# SIDEPANELV5_old.net
KiCad netlist of a schematic drawn in EAGLE
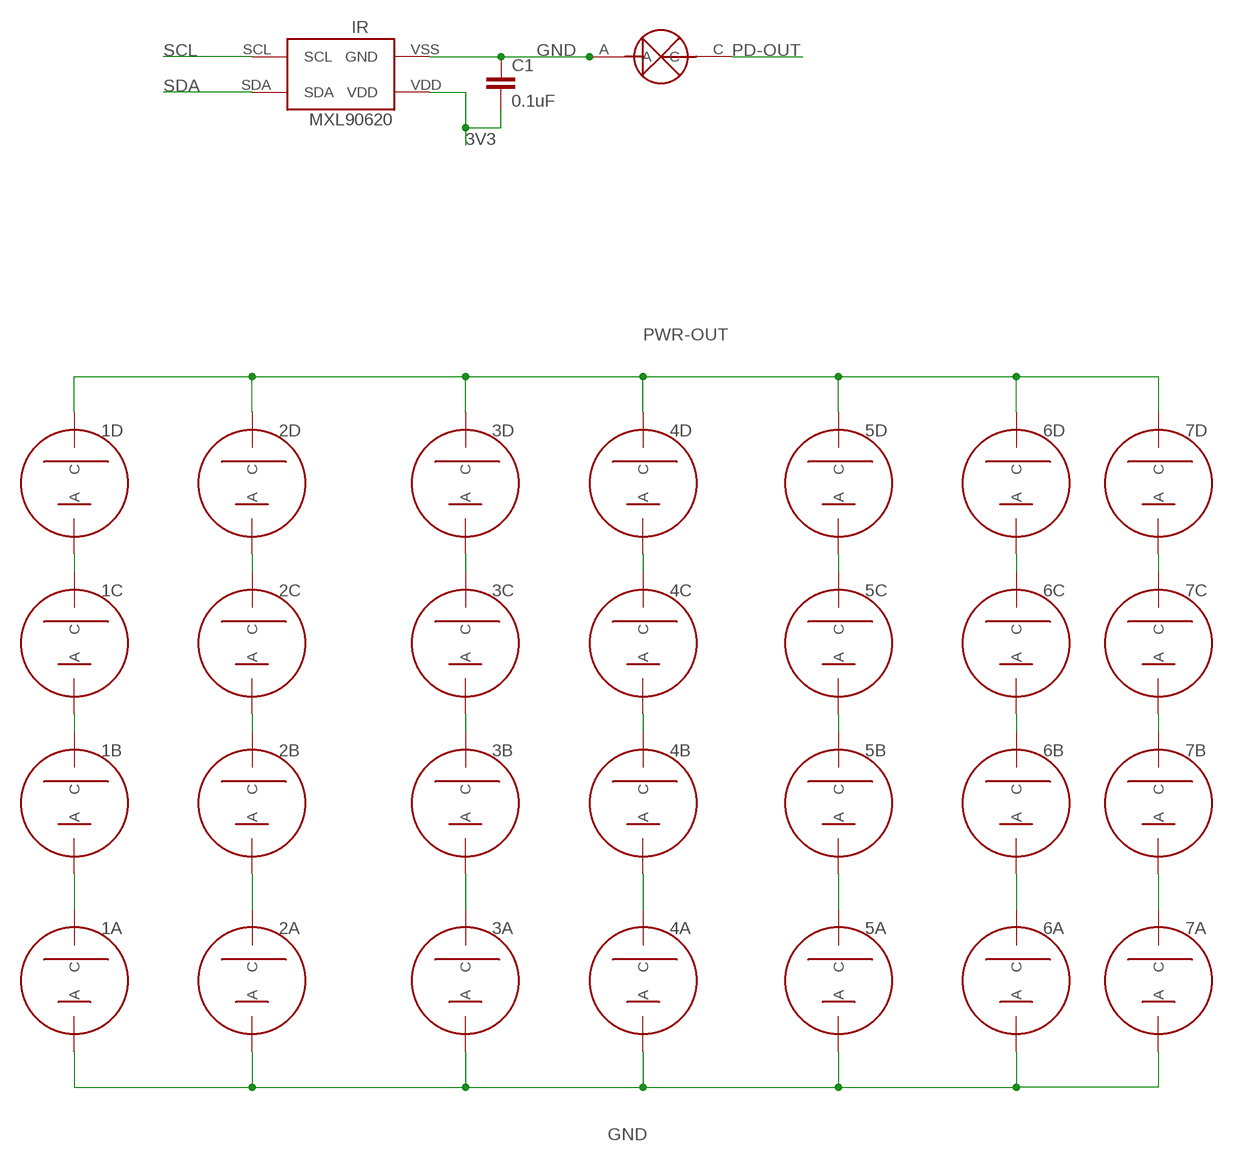
[diagram p0: schematic, sheet 1]

(export (version "E")
  (design (tool "Eeschema 10.0.6"))
  (components
    (comp (ref "1A")
      (value "SOLARCELLV3")
      (footprint "eagle-import:TRISOLX-V3")
      (libsource (lib "eagle-import") (part "SOLARCELLV3"))
    )
    (comp (ref "1B")
      (value "SOLARCELLV3")
      (footprint "eagle-import:TRISOLX-V3")
      (libsource (lib "eagle-import") (part "SOLARCELLV3"))
    )
    (comp (ref "1C")
      (value "SOLARCELLV3")
      (footprint "eagle-import:TRISOLX-V3")
      (libsource (lib "eagle-import") (part "SOLARCELLV3"))
    )
    (comp (ref "1D")
      (value "SOLARCELLV3")
      (footprint "eagle-import:TRISOLX-V3")
      (libsource (lib "eagle-import") (part "SOLARCELLV3"))
    )
    (comp (ref "2A")
      (value "SOLARCELLV3")
      (footprint "eagle-import:TRISOLX-V3")
      (libsource (lib "eagle-import") (part "SOLARCELLV3"))
    )
    (comp (ref "2B")
      (value "SOLARCELLV3")
      (footprint "eagle-import:TRISOLX-V3")
      (libsource (lib "eagle-import") (part "SOLARCELLV3"))
    )
    (comp (ref "2C")
      (value "SOLARCELLV3")
      (footprint "eagle-import:TRISOLX-V3")
      (libsource (lib "eagle-import") (part "SOLARCELLV3"))
    )
    (comp (ref "2D")
      (value "SOLARCELLV3")
      (footprint "eagle-import:TRISOLX-V3")
      (libsource (lib "eagle-import") (part "SOLARCELLV3"))
    )
    (comp (ref "3A")
      (value "SOLARCELLV3")
      (footprint "eagle-import:TRISOLX-V3")
      (libsource (lib "eagle-import") (part "SOLARCELLV3"))
    )
    (comp (ref "3B")
      (value "SOLARCELLV3")
      (footprint "eagle-import:TRISOLX-V3")
      (libsource (lib "eagle-import") (part "SOLARCELLV3"))
    )
    (comp (ref "3C")
      (value "SOLARCELLV3")
      (footprint "eagle-import:TRISOLX-V3")
      (libsource (lib "eagle-import") (part "SOLARCELLV3"))
    )
    (comp (ref "3D")
      (value "SOLARCELLV3")
      (footprint "eagle-import:TRISOLX-V3")
      (libsource (lib "eagle-import") (part "SOLARCELLV3"))
    )
    (comp (ref "4A")
      (value "SOLARCELLV3")
      (footprint "eagle-import:TRISOLX-V3")
      (libsource (lib "eagle-import") (part "SOLARCELLV3"))
    )
    (comp (ref "4B")
      (value "SOLARCELLV3")
      (footprint "eagle-import:TRISOLX-V3")
      (libsource (lib "eagle-import") (part "SOLARCELLV3"))
    )
    (comp (ref "4C")
      (value "SOLARCELLV3")
      (footprint "eagle-import:TRISOLX-V3")
      (libsource (lib "eagle-import") (part "SOLARCELLV3"))
    )
    (comp (ref "4D")
      (value "SOLARCELLV3")
      (footprint "eagle-import:TRISOLX-V3")
      (libsource (lib "eagle-import") (part "SOLARCELLV3"))
    )
    (comp (ref "5A")
      (value "SOLARCELLV3")
      (footprint "eagle-import:TRISOLX-V3")
      (libsource (lib "eagle-import") (part "SOLARCELLV3"))
    )
    (comp (ref "5B")
      (value "SOLARCELLV3")
      (footprint "eagle-import:TRISOLX-V3")
      (libsource (lib "eagle-import") (part "SOLARCELLV3"))
    )
    (comp (ref "5C")
      (value "SOLARCELLV3")
      (footprint "eagle-import:TRISOLX-V3")
      (libsource (lib "eagle-import") (part "SOLARCELLV3"))
    )
    (comp (ref "5D")
      (value "SOLARCELLV3")
      (footprint "eagle-import:TRISOLX-V3")
      (libsource (lib "eagle-import") (part "SOLARCELLV3"))
    )
    (comp (ref "6A")
      (value "SOLARCELLV3")
      (footprint "eagle-import:TRISOLX-V3")
      (libsource (lib "eagle-import") (part "SOLARCELLV3"))
    )
    (comp (ref "6B")
      (value "SOLARCELLV3")
      (footprint "eagle-import:TRISOLX-V3")
      (libsource (lib "eagle-import") (part "SOLARCELLV3"))
    )
    (comp (ref "6C")
      (value "SOLARCELLV3")
      (footprint "eagle-import:TRISOLX-V3")
      (libsource (lib "eagle-import") (part "SOLARCELLV3"))
    )
    (comp (ref "6D")
      (value "SOLARCELLV3")
      (footprint "eagle-import:TRISOLX-V3")
      (libsource (lib "eagle-import") (part "SOLARCELLV3"))
    )
    (comp (ref "7A")
      (value "SOLARCELLV3")
      (footprint "eagle-import:TRISOLX-V3")
      (libsource (lib "eagle-import") (part "SOLARCELLV3"))
    )
    (comp (ref "7B")
      (value "SOLARCELLV3")
      (footprint "eagle-import:TRISOLX-V3")
      (libsource (lib "eagle-import") (part "SOLARCELLV3"))
    )
    (comp (ref "7C")
      (value "SOLARCELLV3")
      (footprint "eagle-import:TRISOLX-V3")
      (libsource (lib "eagle-import") (part "SOLARCELLV3"))
    )
    (comp (ref "7D")
      (value "SOLARCELLV3")
      (footprint "eagle-import:TRISOLX-V3")
      (libsource (lib "eagle-import") (part "SOLARCELLV3"))
    )
    (comp (ref "C1")
      (value "0.1uF")
      (footprint "eagle-import:0805")
      (libsource (lib "eagle-import") (part "CAP0805"))
    )
    (comp (ref "IR")
      (value "MXL90620")
      (footprint "eagle-import:MXL90620")
      (libsource (lib "eagle-import") (part "MXL90620"))
    )
    (comp (ref "PD")
      (value "PHOTODETECTOR")
      (footprint "eagle-import:PHOTODECTORDEVICE2")
      (libsource (lib "eagle-import") (part "PHOTODETECTOR"))
    )
  )
  (nets
    (net (code "1") (name "/3V3") (class "Default")
      (node (ref "C1") (pin "2") (pinfunction "2_2") (pintype "passive"))
      (node (ref "IR") (pin "VDD") (pinfunction "VDD_VDD") (pintype "bidirectional"))
    )
    (net (code "2") (name "/GND") (class "Default")
      (node (ref "1A") (pin "ANODE") (pinfunction "A_ANODE") (pintype "bidirectional"))
      (node (ref "2A") (pin "ANODE") (pinfunction "A_ANODE") (pintype "bidirectional"))
      (node (ref "3A") (pin "ANODE") (pinfunction "A_ANODE") (pintype "bidirectional"))
      (node (ref "4A") (pin "ANODE") (pinfunction "A_ANODE") (pintype "bidirectional"))
      (node (ref "5A") (pin "ANODE") (pinfunction "A_ANODE") (pintype "bidirectional"))
      (node (ref "6A") (pin "ANODE") (pinfunction "A_ANODE") (pintype "bidirectional"))
      (node (ref "7A") (pin "ANODE") (pinfunction "A_ANODE") (pintype "bidirectional"))
      (node (ref "C1") (pin "1") (pinfunction "1_1") (pintype "passive"))
      (node (ref "IR") (pin "VSS") (pinfunction "GND_VSS") (pintype "bidirectional"))
      (node (ref "PD") (pin "A") (pinfunction "A_A") (pintype "bidirectional"))
    )
    (net (code "3") (name "/PD-OUT") (class "Default")
      (node (ref "PD") (pin "C") (pinfunction "C_C") (pintype "bidirectional"))
    )
    (net (code "4") (name "/PWR-OUT") (class "Default")
      (node (ref "1D") (pin "CATHODE") (pinfunction "C_CATHODE") (pintype "bidirectional"))
      (node (ref "2D") (pin "CATHODE") (pinfunction "C_CATHODE") (pintype "bidirectional"))
      (node (ref "3D") (pin "CATHODE") (pinfunction "C_CATHODE") (pintype "bidirectional"))
      (node (ref "4D") (pin "CATHODE") (pinfunction "C_CATHODE") (pintype "bidirectional"))
      (node (ref "5D") (pin "CATHODE") (pinfunction "C_CATHODE") (pintype "bidirectional"))
      (node (ref "6D") (pin "CATHODE") (pinfunction "C_CATHODE") (pintype "bidirectional"))
      (node (ref "7D") (pin "CATHODE") (pinfunction "C_CATHODE") (pintype "bidirectional"))
    )
    (net (code "5") (name "/SCL") (class "Default")
      (node (ref "IR") (pin "SCL") (pinfunction "SCL_SCL") (pintype "bidirectional"))
    )
    (net (code "6") (name "/SDA") (class "Default")
      (node (ref "IR") (pin "SDA") (pinfunction "SDA_SDA") (pintype "bidirectional"))
    )
    (net (code "7") (name "Net-(1A-C)") (class "Default")
      (node (ref "1A") (pin "CATHODE") (pinfunction "C_CATHODE") (pintype "bidirectional"))
      (node (ref "1B") (pin "ANODE") (pinfunction "A_ANODE") (pintype "bidirectional"))
    )
    (net (code "8") (name "Net-(1B-C)") (class "Default")
      (node (ref "1B") (pin "CATHODE") (pinfunction "C_CATHODE") (pintype "bidirectional"))
      (node (ref "1C") (pin "ANODE") (pinfunction "A_ANODE") (pintype "bidirectional"))
    )
    (net (code "9") (name "Net-(1C-C)") (class "Default")
      (node (ref "1C") (pin "CATHODE") (pinfunction "C_CATHODE") (pintype "bidirectional"))
      (node (ref "1D") (pin "ANODE") (pinfunction "A_ANODE") (pintype "bidirectional"))
    )
    (net (code "10") (name "Net-(2A-C)") (class "Default")
      (node (ref "2A") (pin "CATHODE") (pinfunction "C_CATHODE") (pintype "bidirectional"))
      (node (ref "2B") (pin "ANODE") (pinfunction "A_ANODE") (pintype "bidirectional"))
    )
    (net (code "11") (name "Net-(2B-C)") (class "Default")
      (node (ref "2B") (pin "CATHODE") (pinfunction "C_CATHODE") (pintype "bidirectional"))
      (node (ref "2C") (pin "ANODE") (pinfunction "A_ANODE") (pintype "bidirectional"))
    )
    (net (code "12") (name "Net-(2C-C)") (class "Default")
      (node (ref "2C") (pin "CATHODE") (pinfunction "C_CATHODE") (pintype "bidirectional"))
      (node (ref "2D") (pin "ANODE") (pinfunction "A_ANODE") (pintype "bidirectional"))
    )
    (net (code "13") (name "Net-(3A-C)") (class "Default")
      (node (ref "3A") (pin "CATHODE") (pinfunction "C_CATHODE") (pintype "bidirectional"))
      (node (ref "3B") (pin "ANODE") (pinfunction "A_ANODE") (pintype "bidirectional"))
    )
    (net (code "14") (name "Net-(3B-C)") (class "Default")
      (node (ref "3B") (pin "CATHODE") (pinfunction "C_CATHODE") (pintype "bidirectional"))
      (node (ref "3C") (pin "ANODE") (pinfunction "A_ANODE") (pintype "bidirectional"))
    )
    (net (code "15") (name "Net-(3C-C)") (class "Default")
      (node (ref "3C") (pin "CATHODE") (pinfunction "C_CATHODE") (pintype "bidirectional"))
      (node (ref "3D") (pin "ANODE") (pinfunction "A_ANODE") (pintype "bidirectional"))
    )
    (net (code "16") (name "Net-(4A-C)") (class "Default")
      (node (ref "4A") (pin "CATHODE") (pinfunction "C_CATHODE") (pintype "bidirectional"))
      (node (ref "4B") (pin "ANODE") (pinfunction "A_ANODE") (pintype "bidirectional"))
    )
    (net (code "17") (name "Net-(4B-C)") (class "Default")
      (node (ref "4B") (pin "CATHODE") (pinfunction "C_CATHODE") (pintype "bidirectional"))
      (node (ref "4C") (pin "ANODE") (pinfunction "A_ANODE") (pintype "bidirectional"))
    )
    (net (code "18") (name "Net-(4C-C)") (class "Default")
      (node (ref "4C") (pin "CATHODE") (pinfunction "C_CATHODE") (pintype "bidirectional"))
      (node (ref "4D") (pin "ANODE") (pinfunction "A_ANODE") (pintype "bidirectional"))
    )
    (net (code "19") (name "Net-(5A-C)") (class "Default")
      (node (ref "5A") (pin "CATHODE") (pinfunction "C_CATHODE") (pintype "bidirectional"))
      (node (ref "5B") (pin "ANODE") (pinfunction "A_ANODE") (pintype "bidirectional"))
    )
    (net (code "20") (name "Net-(5B-C)") (class "Default")
      (node (ref "5B") (pin "CATHODE") (pinfunction "C_CATHODE") (pintype "bidirectional"))
      (node (ref "5C") (pin "ANODE") (pinfunction "A_ANODE") (pintype "bidirectional"))
    )
    (net (code "21") (name "Net-(5C-C)") (class "Default")
      (node (ref "5C") (pin "CATHODE") (pinfunction "C_CATHODE") (pintype "bidirectional"))
      (node (ref "5D") (pin "ANODE") (pinfunction "A_ANODE") (pintype "bidirectional"))
    )
    (net (code "22") (name "Net-(6A-C)") (class "Default")
      (node (ref "6A") (pin "CATHODE") (pinfunction "C_CATHODE") (pintype "bidirectional"))
      (node (ref "6B") (pin "ANODE") (pinfunction "A_ANODE") (pintype "bidirectional"))
    )
    (net (code "23") (name "Net-(6B-C)") (class "Default")
      (node (ref "6B") (pin "CATHODE") (pinfunction "C_CATHODE") (pintype "bidirectional"))
      (node (ref "6C") (pin "ANODE") (pinfunction "A_ANODE") (pintype "bidirectional"))
    )
    (net (code "24") (name "Net-(6C-C)") (class "Default")
      (node (ref "6C") (pin "CATHODE") (pinfunction "C_CATHODE") (pintype "bidirectional"))
      (node (ref "6D") (pin "ANODE") (pinfunction "A_ANODE") (pintype "bidirectional"))
    )
    (net (code "25") (name "Net-(7A-C)") (class "Default")
      (node (ref "7A") (pin "CATHODE") (pinfunction "C_CATHODE") (pintype "bidirectional"))
      (node (ref "7B") (pin "ANODE") (pinfunction "A_ANODE") (pintype "bidirectional"))
    )
    (net (code "26") (name "Net-(7B-C)") (class "Default")
      (node (ref "7B") (pin "CATHODE") (pinfunction "C_CATHODE") (pintype "bidirectional"))
      (node (ref "7C") (pin "ANODE") (pinfunction "A_ANODE") (pintype "bidirectional"))
    )
    (net (code "27") (name "Net-(7C-C)") (class "Default")
      (node (ref "7C") (pin "CATHODE") (pinfunction "C_CATHODE") (pintype "bidirectional"))
      (node (ref "7D") (pin "ANODE") (pinfunction "A_ANODE") (pintype "bidirectional"))
    )
  )
)
